# LED_Monitor.net
KiCad netlist of a schematic drawn in Altium Designer
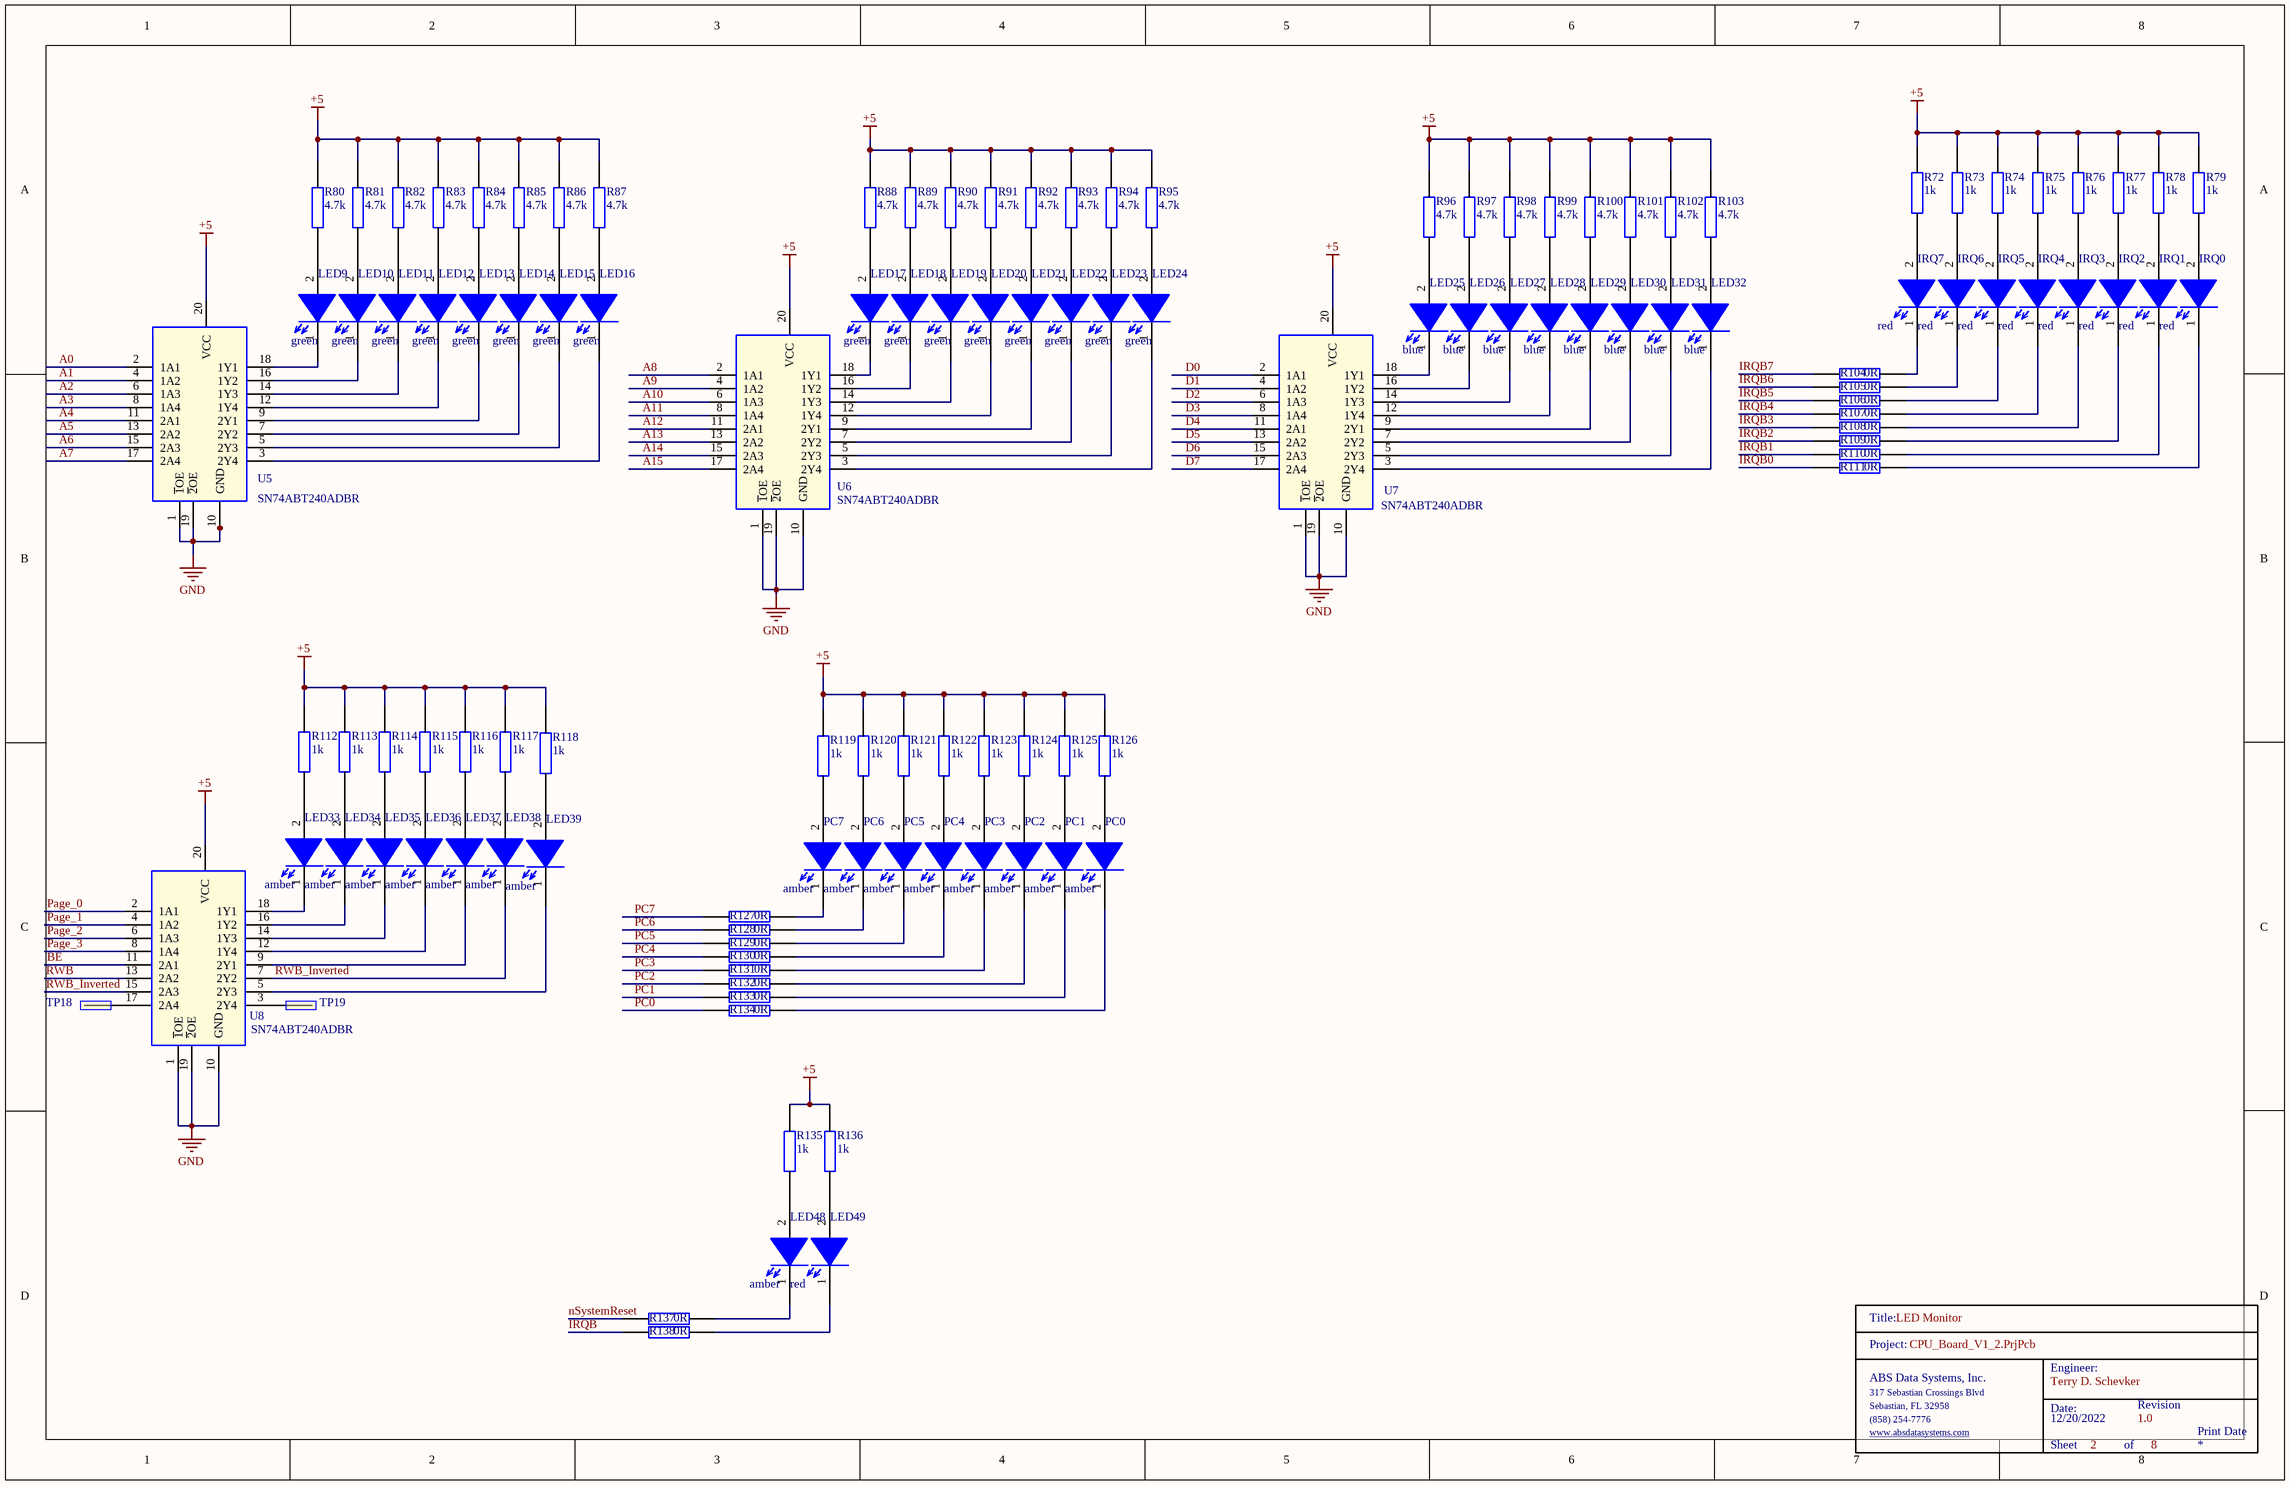
[diagram p0: LED_Monitor.SchDoc]

(export (version "E")
  (design (tool "Eeschema 10.0.6"))
  (components
    (comp (ref "IRQ0")
      (value "red")
      (footprint "0603_Diode")
      (description "Wurth Elektronik 0603 red")
      (fields
        (field (name "MANUFACTURER") "Wurth Electronics")
        (field (name "MANUFACTURER PART NUMBER") "150060GS75000")
      )
      (libsource (lib "Misc") (part "150060RS75000"))
    )
    (comp (ref "IRQ1")
      (value "red")
      (footprint "0603_Diode")
      (description "Wurth Elektronik 0603 red")
      (fields
        (field (name "MANUFACTURER") "Wurth Electronics")
        (field (name "MANUFACTURER PART NUMBER") "150060GS75000")
      )
      (libsource (lib "Misc") (part "150060RS75000"))
    )
    (comp (ref "IRQ2")
      (value "red")
      (footprint "0603_Diode")
      (description "Wurth Elektronik 0603 red")
      (fields
        (field (name "MANUFACTURER") "Wurth Electronics")
        (field (name "MANUFACTURER PART NUMBER") "150060GS75000")
      )
      (libsource (lib "Misc") (part "150060RS75000"))
    )
    (comp (ref "IRQ3")
      (value "red")
      (footprint "0603_Diode")
      (description "Wurth Elektronik 0603 red")
      (fields
        (field (name "MANUFACTURER") "Wurth Electronics")
        (field (name "MANUFACTURER PART NUMBER") "150060GS75000")
      )
      (libsource (lib "Misc") (part "150060RS75000"))
    )
    (comp (ref "IRQ4")
      (value "red")
      (footprint "0603_Diode")
      (description "Wurth Elektronik 0603 red")
      (fields
        (field (name "MANUFACTURER") "Wurth Electronics")
        (field (name "MANUFACTURER PART NUMBER") "150060GS75000")
      )
      (libsource (lib "Misc") (part "150060RS75000"))
    )
    (comp (ref "IRQ5")
      (value "red")
      (footprint "0603_Diode")
      (description "Wurth Elektronik 0603 red")
      (fields
        (field (name "MANUFACTURER") "Wurth Electronics")
        (field (name "MANUFACTURER PART NUMBER") "150060GS75000")
      )
      (libsource (lib "Misc") (part "150060RS75000"))
    )
    (comp (ref "IRQ6")
      (value "red")
      (footprint "0603_Diode")
      (description "Wurth Elektronik 0603 red")
      (fields
        (field (name "MANUFACTURER") "Wurth Electronics")
        (field (name "MANUFACTURER PART NUMBER") "150060GS75000")
      )
      (libsource (lib "Misc") (part "150060RS75000"))
    )
    (comp (ref "IRQ7")
      (value "red")
      (footprint "0603_Diode")
      (description "Wurth Elektronik 0603 red")
      (fields
        (field (name "MANUFACTURER") "Wurth Electronics")
        (field (name "MANUFACTURER PART NUMBER") "150060GS75000")
      )
      (libsource (lib "Misc") (part "150060RS75000"))
    )
    (comp (ref "LED9")
      (value "green")
      (footprint "0603_Diode")
      (description "Wurth Elektronik 0603 green")
      (fields
        (field (name "MANUFACTURER") "Wurth Electronics")
        (field (name "MANUFACTURER PART NUMBER") "150060GS75000")
      )
      (libsource (lib "Misc") (part "150060GS75000"))
    )
    (comp (ref "LED10")
      (value "green")
      (footprint "0603_Diode")
      (description "Wurth Elektronik 0603 green")
      (fields
        (field (name "MANUFACTURER") "Wurth Electronics")
        (field (name "MANUFACTURER PART NUMBER") "150060GS75000")
      )
      (libsource (lib "Misc") (part "150060GS75000"))
    )
    (comp (ref "LED11")
      (value "green")
      (footprint "0603_Diode")
      (description "Wurth Elektronik 0603 green")
      (fields
        (field (name "MANUFACTURER") "Wurth Electronics")
        (field (name "MANUFACTURER PART NUMBER") "150060GS75000")
      )
      (libsource (lib "Misc") (part "150060GS75000"))
    )
    (comp (ref "LED12")
      (value "green")
      (footprint "0603_Diode")
      (description "Wurth Elektronik 0603 green")
      (fields
        (field (name "MANUFACTURER") "Wurth Electronics")
        (field (name "MANUFACTURER PART NUMBER") "150060GS75000")
      )
      (libsource (lib "Misc") (part "150060GS75000"))
    )
    (comp (ref "LED13")
      (value "green")
      (footprint "0603_Diode")
      (description "Wurth Elektronik 0603 green")
      (fields
        (field (name "MANUFACTURER") "Wurth Electronics")
        (field (name "MANUFACTURER PART NUMBER") "150060GS75000")
      )
      (libsource (lib "Misc") (part "150060GS75000"))
    )
    (comp (ref "LED14")
      (value "green")
      (footprint "0603_Diode")
      (description "Wurth Elektronik 0603 green")
      (fields
        (field (name "MANUFACTURER") "Wurth Electronics")
        (field (name "MANUFACTURER PART NUMBER") "150060GS75000")
      )
      (libsource (lib "Misc") (part "150060GS75000"))
    )
    (comp (ref "LED15")
      (value "green")
      (footprint "0603_Diode")
      (description "Wurth Elektronik 0603 green")
      (fields
        (field (name "MANUFACTURER") "Wurth Electronics")
        (field (name "MANUFACTURER PART NUMBER") "150060GS75000")
      )
      (libsource (lib "Misc") (part "150060GS75000"))
    )
    (comp (ref "LED16")
      (value "green")
      (footprint "0603_Diode")
      (description "Wurth Elektronik 0603 green")
      (fields
        (field (name "MANUFACTURER") "Wurth Electronics")
        (field (name "MANUFACTURER PART NUMBER") "150060GS75000")
      )
      (libsource (lib "Misc") (part "150060GS75000"))
    )
    (comp (ref "LED17")
      (value "green")
      (footprint "0603_Diode")
      (description "Wurth Elektronik 0603 green")
      (fields
        (field (name "MANUFACTURER") "Wurth Electronics")
        (field (name "MANUFACTURER PART NUMBER") "150060GS75000")
      )
      (libsource (lib "Misc") (part "150060GS75000"))
    )
    (comp (ref "LED18")
      (value "green")
      (footprint "0603_Diode")
      (description "Wurth Elektronik 0603 green")
      (fields
        (field (name "MANUFACTURER") "Wurth Electronics")
        (field (name "MANUFACTURER PART NUMBER") "150060GS75000")
      )
      (libsource (lib "Misc") (part "150060GS75000"))
    )
    (comp (ref "LED19")
      (value "green")
      (footprint "0603_Diode")
      (description "Wurth Elektronik 0603 green")
      (fields
        (field (name "MANUFACTURER") "Wurth Electronics")
        (field (name "MANUFACTURER PART NUMBER") "150060GS75000")
      )
      (libsource (lib "Misc") (part "150060GS75000"))
    )
    (comp (ref "LED20")
      (value "green")
      (footprint "0603_Diode")
      (description "Wurth Elektronik 0603 green")
      (fields
        (field (name "MANUFACTURER") "Wurth Electronics")
        (field (name "MANUFACTURER PART NUMBER") "150060GS75000")
      )
      (libsource (lib "Misc") (part "150060GS75000"))
    )
    (comp (ref "LED21")
      (value "green")
      (footprint "0603_Diode")
      (description "Wurth Elektronik 0603 green")
      (fields
        (field (name "MANUFACTURER") "Wurth Electronics")
        (field (name "MANUFACTURER PART NUMBER") "150060GS75000")
      )
      (libsource (lib "Misc") (part "150060GS75000"))
    )
    (comp (ref "LED22")
      (value "green")
      (footprint "0603_Diode")
      (description "Wurth Elektronik 0603 green")
      (fields
        (field (name "MANUFACTURER") "Wurth Electronics")
        (field (name "MANUFACTURER PART NUMBER") "150060GS75000")
      )
      (libsource (lib "Misc") (part "150060GS75000"))
    )
    (comp (ref "LED23")
      (value "green")
      (footprint "0603_Diode")
      (description "Wurth Elektronik 0603 green")
      (fields
        (field (name "MANUFACTURER") "Wurth Electronics")
        (field (name "MANUFACTURER PART NUMBER") "150060GS75000")
      )
      (libsource (lib "Misc") (part "150060GS75000"))
    )
    (comp (ref "LED24")
      (value "green")
      (footprint "0603_Diode")
      (description "Wurth Elektronik 0603 green")
      (fields
        (field (name "MANUFACTURER") "Wurth Electronics")
        (field (name "MANUFACTURER PART NUMBER") "150060GS75000")
      )
      (libsource (lib "Misc") (part "150060GS75000"))
    )
    (comp (ref "LED25")
      (value "blue")
      (footprint "0603_Diode")
      (description "Wurth Elektronik 0603 blue")
      (fields
        (field (name "MANUFACTURER") "Wurth Electronics")
        (field (name "MANUFACTURER PART NUMBER") "150060GS75000")
      )
      (libsource (lib "Misc") (part "150060BS75000"))
    )
    (comp (ref "LED26")
      (value "blue")
      (footprint "0603_Diode")
      (description "Wurth Elektronik 0603 blue")
      (fields
        (field (name "MANUFACTURER") "Wurth Electronics")
        (field (name "MANUFACTURER PART NUMBER") "150060GS75000")
      )
      (libsource (lib "Misc") (part "150060BS75000"))
    )
    (comp (ref "LED27")
      (value "blue")
      (footprint "0603_Diode")
      (description "Wurth Elektronik 0603 blue")
      (fields
        (field (name "MANUFACTURER") "Wurth Electronics")
        (field (name "MANUFACTURER PART NUMBER") "150060GS75000")
      )
      (libsource (lib "Misc") (part "150060BS75000"))
    )
    (comp (ref "LED28")
      (value "blue")
      (footprint "0603_Diode")
      (description "Wurth Elektronik 0603 blue")
      (fields
        (field (name "MANUFACTURER") "Wurth Electronics")
        (field (name "MANUFACTURER PART NUMBER") "150060GS75000")
      )
      (libsource (lib "Misc") (part "150060BS75000"))
    )
    (comp (ref "LED29")
      (value "blue")
      (footprint "0603_Diode")
      (description "Wurth Elektronik 0603 blue")
      (fields
        (field (name "MANUFACTURER") "Wurth Electronics")
        (field (name "MANUFACTURER PART NUMBER") "150060GS75000")
      )
      (libsource (lib "Misc") (part "150060BS75000"))
    )
    (comp (ref "LED30")
      (value "blue")
      (footprint "0603_Diode")
      (description "Wurth Elektronik 0603 blue")
      (fields
        (field (name "MANUFACTURER") "Wurth Electronics")
        (field (name "MANUFACTURER PART NUMBER") "150060GS75000")
      )
      (libsource (lib "Misc") (part "150060BS75000"))
    )
    (comp (ref "LED31")
      (value "blue")
      (footprint "0603_Diode")
      (description "Wurth Elektronik 0603 blue")
      (fields
        (field (name "MANUFACTURER") "Wurth Electronics")
        (field (name "MANUFACTURER PART NUMBER") "150060GS75000")
      )
      (libsource (lib "Misc") (part "150060BS75000"))
    )
    (comp (ref "LED32")
      (value "blue")
      (footprint "0603_Diode")
      (description "Wurth Elektronik 0603 blue")
      (fields
        (field (name "MANUFACTURER") "Wurth Electronics")
        (field (name "MANUFACTURER PART NUMBER") "150060GS75000")
      )
      (libsource (lib "Misc") (part "150060BS75000"))
    )
    (comp (ref "LED33")
      (value "amber")
      (footprint "0603_Diode")
      (description "Wurth Elektronik 0603 amber")
      (fields
        (field (name "MANUFACTURER") "Wurth Electronics")
        (field (name "MANUFACTURER PART NUMBER") "150060GS75000")
      )
      (libsource (lib "Misc") (part "150060AS75000"))
    )
    (comp (ref "LED34")
      (value "amber")
      (footprint "0603_Diode")
      (description "Wurth Elektronik 0603 amber")
      (fields
        (field (name "MANUFACTURER") "Wurth Electronics")
        (field (name "MANUFACTURER PART NUMBER") "150060GS75000")
      )
      (libsource (lib "Misc") (part "150060AS75000"))
    )
    (comp (ref "LED35")
      (value "amber")
      (footprint "0603_Diode")
      (description "Wurth Elektronik 0603 amber")
      (fields
        (field (name "MANUFACTURER") "Wurth Electronics")
        (field (name "MANUFACTURER PART NUMBER") "150060GS75000")
      )
      (libsource (lib "Misc") (part "150060AS75000"))
    )
    (comp (ref "LED36")
      (value "amber")
      (footprint "0603_Diode")
      (description "Wurth Elektronik 0603 amber")
      (fields
        (field (name "MANUFACTURER") "Wurth Electronics")
        (field (name "MANUFACTURER PART NUMBER") "150060GS75000")
      )
      (libsource (lib "Misc") (part "150060AS75000"))
    )
    (comp (ref "LED37")
      (value "amber")
      (footprint "0603_Diode")
      (description "Wurth Elektronik 0603 amber")
      (fields
        (field (name "MANUFACTURER") "Wurth Electronics")
        (field (name "MANUFACTURER PART NUMBER") "150060GS75000")
      )
      (libsource (lib "Misc") (part "150060AS75000"))
    )
    (comp (ref "LED38")
      (value "amber")
      (footprint "0603_Diode")
      (description "Wurth Elektronik 0603 amber")
      (fields
        (field (name "MANUFACTURER") "Wurth Electronics")
        (field (name "MANUFACTURER PART NUMBER") "150060GS75000")
      )
      (libsource (lib "Misc") (part "150060AS75000"))
    )
    (comp (ref "LED39")
      (value "amber")
      (footprint "0603_Diode")
      (description "Wurth Elektronik 0603 amber")
      (fields
        (field (name "MANUFACTURER") "Wurth Electronics")
        (field (name "MANUFACTURER PART NUMBER") "150060GS75000")
      )
      (libsource (lib "Misc") (part "150060AS75000"))
    )
    (comp (ref "LED48")
      (value "amber")
      (footprint "0603_Diode")
      (description "Wurth Elektronik 0603 amber")
      (fields
        (field (name "MANUFACTURER") "Wurth Electronics")
        (field (name "MANUFACTURER PART NUMBER") "150060GS75000")
      )
      (libsource (lib "Misc") (part "150060AS75000"))
    )
    (comp (ref "LED49")
      (value "red")
      (footprint "0603_Diode")
      (description "Wurth Elektronik 0603 red")
      (fields
        (field (name "MANUFACTURER") "Wurth Electronics")
        (field (name "MANUFACTURER PART NUMBER") "150060GS75000")
      )
      (libsource (lib "Misc") (part "150060RS75000"))
    )
    (comp (ref "PC0")
      (value "amber")
      (footprint "0603_Diode")
      (description "Wurth Elektronik 0603 amber")
      (fields
        (field (name "MANUFACTURER") "Wurth Electronics")
        (field (name "MANUFACTURER PART NUMBER") "150060GS75000")
      )
      (libsource (lib "Misc") (part "150060AS75000"))
    )
    (comp (ref "PC1")
      (value "amber")
      (footprint "0603_Diode")
      (description "Wurth Elektronik 0603 amber")
      (fields
        (field (name "MANUFACTURER") "Wurth Electronics")
        (field (name "MANUFACTURER PART NUMBER") "150060GS75000")
      )
      (libsource (lib "Misc") (part "150060AS75000"))
    )
    (comp (ref "PC2")
      (value "amber")
      (footprint "0603_Diode")
      (description "Wurth Elektronik 0603 amber")
      (fields
        (field (name "MANUFACTURER") "Wurth Electronics")
        (field (name "MANUFACTURER PART NUMBER") "150060GS75000")
      )
      (libsource (lib "Misc") (part "150060AS75000"))
    )
    (comp (ref "PC3")
      (value "amber")
      (footprint "0603_Diode")
      (description "Wurth Elektronik 0603 amber")
      (fields
        (field (name "MANUFACTURER") "Wurth Electronics")
        (field (name "MANUFACTURER PART NUMBER") "150060GS75000")
      )
      (libsource (lib "Misc") (part "150060AS75000"))
    )
    (comp (ref "PC4")
      (value "amber")
      (footprint "0603_Diode")
      (description "Wurth Elektronik 0603 amber")
      (fields
        (field (name "MANUFACTURER") "Wurth Electronics")
        (field (name "MANUFACTURER PART NUMBER") "150060GS75000")
      )
      (libsource (lib "Misc") (part "150060AS75000"))
    )
    (comp (ref "PC5")
      (value "amber")
      (footprint "0603_Diode")
      (description "Wurth Elektronik 0603 amber")
      (fields
        (field (name "MANUFACTURER") "Wurth Electronics")
        (field (name "MANUFACTURER PART NUMBER") "150060GS75000")
      )
      (libsource (lib "Misc") (part "150060AS75000"))
    )
    (comp (ref "PC6")
      (value "amber")
      (footprint "0603_Diode")
      (description "Wurth Elektronik 0603 amber")
      (fields
        (field (name "MANUFACTURER") "Wurth Electronics")
        (field (name "MANUFACTURER PART NUMBER") "150060GS75000")
      )
      (libsource (lib "Misc") (part "150060AS75000"))
    )
    (comp (ref "PC7")
      (value "amber")
      (footprint "0603_Diode")
      (description "Wurth Elektronik 0603 amber")
      (fields
        (field (name "MANUFACTURER") "Wurth Electronics")
        (field (name "MANUFACTURER PART NUMBER") "150060GS75000")
      )
      (libsource (lib "Misc") (part "150060AS75000"))
    )
    (comp (ref "R72")
      (value "1k")
      (footprint "0603")
      (description "YAGEO 0603 1k ohm")
      (fields
        (field (name "MOUSER PART NUMBER") "603-RC0603JR-070RL")
        (field (name "MANUFACTURER_PART_NUMBER") "RC0603JR-070RL")
      )
      (libsource (lib "Resistors") (part "AC0603FR-7W1KL_1"))
    )
    (comp (ref "R73")
      (value "1k")
      (footprint "0603")
      (description "YAGEO 0603 1k ohm")
      (fields
        (field (name "MOUSER PART NUMBER") "603-RC0603JR-070RL")
        (field (name "MANUFACTURER_PART_NUMBER") "RC0603JR-070RL")
      )
      (libsource (lib "Resistors") (part "AC0603FR-7W1KL_1"))
    )
    (comp (ref "R74")
      (value "1k")
      (footprint "0603")
      (description "YAGEO 0603 1k ohm")
      (fields
        (field (name "MOUSER PART NUMBER") "603-RC0603JR-070RL")
        (field (name "MANUFACTURER_PART_NUMBER") "RC0603JR-070RL")
      )
      (libsource (lib "Resistors") (part "AC0603FR-7W1KL_1"))
    )
    (comp (ref "R75")
      (value "1k")
      (footprint "0603")
      (description "YAGEO 0603 1k ohm")
      (fields
        (field (name "MOUSER PART NUMBER") "603-RC0603JR-070RL")
        (field (name "MANUFACTURER_PART_NUMBER") "RC0603JR-070RL")
      )
      (libsource (lib "Resistors") (part "AC0603FR-7W1KL_1"))
    )
    (comp (ref "R76")
      (value "1k")
      (footprint "0603")
      (description "YAGEO 0603 1k ohm")
      (fields
        (field (name "MOUSER PART NUMBER") "603-RC0603JR-070RL")
        (field (name "MANUFACTURER_PART_NUMBER") "RC0603JR-070RL")
      )
      (libsource (lib "Resistors") (part "AC0603FR-7W1KL_1"))
    )
    (comp (ref "R77")
      (value "1k")
      (footprint "0603")
      (description "YAGEO 0603 1k ohm")
      (fields
        (field (name "MOUSER PART NUMBER") "603-RC0603JR-070RL")
        (field (name "MANUFACTURER_PART_NUMBER") "RC0603JR-070RL")
      )
      (libsource (lib "Resistors") (part "AC0603FR-7W1KL_1"))
    )
    (comp (ref "R78")
      (value "1k")
      (footprint "0603")
      (description "YAGEO 0603 1k ohm")
      (fields
        (field (name "MOUSER PART NUMBER") "603-RC0603JR-070RL")
        (field (name "MANUFACTURER_PART_NUMBER") "RC0603JR-070RL")
      )
      (libsource (lib "Resistors") (part "AC0603FR-7W1KL_1"))
    )
    (comp (ref "R79")
      (value "1k")
      (footprint "0603")
      (description "YAGEO 0603 1k ohm")
      (fields
        (field (name "MOUSER PART NUMBER") "603-RC0603JR-070RL")
        (field (name "MANUFACTURER_PART_NUMBER") "RC0603JR-070RL")
      )
      (libsource (lib "Resistors") (part "AC0603FR-7W1KL_1"))
    )
    (comp (ref "R80")
      (value "4.7k")
      (footprint "0603")
      (description "YAGEO 0603 4.7k")
      (fields
        (field (name "MOUSER PART NUMBER") "603-RC0603JR-070RL")
        (field (name "MANUFACTURER_PART_NUMBER") "RC0603JR-070RL")
      )
      (libsource (lib "Resistors") (part "RC0603FR-104K7L"))
    )
    (comp (ref "R81")
      (value "4.7k")
      (footprint "0603")
      (description "YAGEO 0603 4.7k")
      (fields
        (field (name "MOUSER PART NUMBER") "603-RC0603JR-070RL")
        (field (name "MANUFACTURER_PART_NUMBER") "RC0603JR-070RL")
      )
      (libsource (lib "Resistors") (part "RC0603FR-104K7L"))
    )
    (comp (ref "R82")
      (value "4.7k")
      (footprint "0603")
      (description "YAGEO 0603 4.7k")
      (fields
        (field (name "MOUSER PART NUMBER") "603-RC0603JR-070RL")
        (field (name "MANUFACTURER_PART_NUMBER") "RC0603JR-070RL")
      )
      (libsource (lib "Resistors") (part "RC0603FR-104K7L"))
    )
    (comp (ref "R83")
      (value "4.7k")
      (footprint "0603")
      (description "YAGEO 0603 4.7k")
      (fields
        (field (name "MOUSER PART NUMBER") "603-RC0603JR-070RL")
        (field (name "MANUFACTURER_PART_NUMBER") "RC0603JR-070RL")
      )
      (libsource (lib "Resistors") (part "RC0603FR-104K7L"))
    )
    (comp (ref "R84")
      (value "4.7k")
      (footprint "0603")
      (description "YAGEO 0603 4.7k")
      (fields
        (field (name "MOUSER PART NUMBER") "603-RC0603JR-070RL")
        (field (name "MANUFACTURER_PART_NUMBER") "RC0603JR-070RL")
      )
      (libsource (lib "Resistors") (part "RC0603FR-104K7L"))
    )
    (comp (ref "R85")
      (value "4.7k")
      (footprint "0603")
      (description "YAGEO 0603 4.7k")
      (fields
        (field (name "MOUSER PART NUMBER") "603-RC0603JR-070RL")
        (field (name "MANUFACTURER_PART_NUMBER") "RC0603JR-070RL")
      )
      (libsource (lib "Resistors") (part "RC0603FR-104K7L"))
    )
    (comp (ref "R86")
      (value "4.7k")
      (footprint "0603")
      (description "YAGEO 0603 4.7k")
      (fields
        (field (name "MOUSER PART NUMBER") "603-RC0603JR-070RL")
        (field (name "MANUFACTURER_PART_NUMBER") "RC0603JR-070RL")
      )
      (libsource (lib "Resistors") (part "RC0603FR-104K7L"))
    )
    (comp (ref "R87")
      (value "4.7k")
      (footprint "0603")
      (description "YAGEO 0603 4.7k")
      (fields
        (field (name "MOUSER PART NUMBER") "603-RC0603JR-070RL")
        (field (name "MANUFACTURER_PART_NUMBER") "RC0603JR-070RL")
      )
      (libsource (lib "Resistors") (part "RC0603FR-104K7L"))
    )
    (comp (ref "R88")
      (value "4.7k")
      (footprint "0603")
      (description "YAGEO 0603 4.7k")
      (fields
        (field (name "MOUSER PART NUMBER") "603-RC0603JR-070RL")
        (field (name "MANUFACTURER_PART_NUMBER") "RC0603JR-070RL")
      )
      (libsource (lib "Resistors") (part "RC0603FR-104K7L"))
    )
    (comp (ref "R89")
      (value "4.7k")
      (footprint "0603")
      (description "YAGEO 0603 4.7k")
      (fields
        (field (name "MOUSER PART NUMBER") "603-RC0603JR-070RL")
        (field (name "MANUFACTURER_PART_NUMBER") "RC0603JR-070RL")
      )
      (libsource (lib "Resistors") (part "RC0603FR-104K7L"))
    )
    (comp (ref "R90")
      (value "4.7k")
      (footprint "0603")
      (description "YAGEO 0603 4.7k")
      (fields
        (field (name "MOUSER PART NUMBER") "603-RC0603JR-070RL")
        (field (name "MANUFACTURER_PART_NUMBER") "RC0603JR-070RL")
      )
      (libsource (lib "Resistors") (part "RC0603FR-104K7L"))
    )
    (comp (ref "R91")
      (value "4.7k")
      (footprint "0603")
      (description "YAGEO 0603 4.7k")
      (fields
        (field (name "MOUSER PART NUMBER") "603-RC0603JR-070RL")
        (field (name "MANUFACTURER_PART_NUMBER") "RC0603JR-070RL")
      )
      (libsource (lib "Resistors") (part "RC0603FR-104K7L"))
    )
    (comp (ref "R92")
      (value "4.7k")
      (footprint "0603")
      (description "YAGEO 0603 4.7k")
      (fields
        (field (name "MOUSER PART NUMBER") "603-RC0603JR-070RL")
        (field (name "MANUFACTURER_PART_NUMBER") "RC0603JR-070RL")
      )
      (libsource (lib "Resistors") (part "RC0603FR-104K7L"))
    )
    (comp (ref "R93")
      (value "4.7k")
      (footprint "0603")
      (description "YAGEO 0603 4.7k")
      (fields
        (field (name "MOUSER PART NUMBER") "603-RC0603JR-070RL")
        (field (name "MANUFACTURER_PART_NUMBER") "RC0603JR-070RL")
      )
      (libsource (lib "Resistors") (part "RC0603FR-104K7L"))
    )
    (comp (ref "R94")
      (value "4.7k")
      (footprint "0603")
      (description "YAGEO 0603 4.7k")
      (fields
        (field (name "MOUSER PART NUMBER") "603-RC0603JR-070RL")
        (field (name "MANUFACTURER_PART_NUMBER") "RC0603JR-070RL")
      )
      (libsource (lib "Resistors") (part "RC0603FR-104K7L"))
    )
    (comp (ref "R95")
      (value "4.7k")
      (footprint "0603")
      (description "YAGEO 0603 4.7k")
      (fields
        (field (name "MOUSER PART NUMBER") "603-RC0603JR-070RL")
        (field (name "MANUFACTURER_PART_NUMBER") "RC0603JR-070RL")
      )
      (libsource (lib "Resistors") (part "RC0603FR-104K7L"))
    )
    (comp (ref "R96")
      (value "4.7k")
      (footprint "0603")
      (description "YAGEO 0603 4.7k")
      (fields
        (field (name "MOUSER PART NUMBER") "603-RC0603JR-070RL")
        (field (name "MANUFACTURER_PART_NUMBER") "RC0603JR-070RL")
      )
      (libsource (lib "Resistors") (part "RC0603FR-104K7L"))
    )
    (comp (ref "R97")
      (value "4.7k")
      (footprint "0603")
      (description "YAGEO 0603 4.7k")
      (fields
        (field (name "MOUSER PART NUMBER") "603-RC0603JR-070RL")
        (field (name "MANUFACTURER_PART_NUMBER") "RC0603JR-070RL")
      )
      (libsource (lib "Resistors") (part "RC0603FR-104K7L"))
    )
    (comp (ref "R98")
      (value "4.7k")
      (footprint "0603")
      (description "YAGEO 0603 4.7k")
      (fields
        (field (name "MOUSER PART NUMBER") "603-RC0603JR-070RL")
        (field (name "MANUFACTURER_PART_NUMBER") "RC0603JR-070RL")
      )
      (libsource (lib "Resistors") (part "RC0603FR-104K7L"))
    )
    (comp (ref "R99")
      (value "4.7k")
      (footprint "0603")
      (description "YAGEO 0603 4.7k")
      (fields
        (field (name "MOUSER PART NUMBER") "603-RC0603JR-070RL")
        (field (name "MANUFACTURER_PART_NUMBER") "RC0603JR-070RL")
      )
      (libsource (lib "Resistors") (part "RC0603FR-104K7L"))
    )
    (comp (ref "R100")
      (value "4.7k")
      (footprint "0603")
      (description "YAGEO 0603 4.7k")
      (fields
        (field (name "MOUSER PART NUMBER") "603-RC0603JR-070RL")
        (field (name "MANUFACTURER_PART_NUMBER") "RC0603JR-070RL")
      )
      (libsource (lib "Resistors") (part "RC0603FR-104K7L"))
    )
    (comp (ref "R101")
      (value "4.7k")
      (footprint "0603")
      (description "YAGEO 0603 4.7k")
      (fields
        (field (name "MOUSER PART NUMBER") "603-RC0603JR-070RL")
        (field (name "MANUFACTURER_PART_NUMBER") "RC0603JR-070RL")
      )
      (libsource (lib "Resistors") (part "RC0603FR-104K7L"))
    )
    (comp (ref "R102")
      (value "4.7k")
      (footprint "0603")
      (description "YAGEO 0603 4.7k")
      (fields
        (field (name "MOUSER PART NUMBER") "603-RC0603JR-070RL")
        (field (name "MANUFACTURER_PART_NUMBER") "RC0603JR-070RL")
      )
      (libsource (lib "Resistors") (part "RC0603FR-104K7L"))
    )
    (comp (ref "R103")
      (value "4.7k")
      (footprint "0603")
      (description "YAGEO 0603 4.7k")
      (fields
        (field (name "MOUSER PART NUMBER") "603-RC0603JR-070RL")
        (field (name "MANUFACTURER_PART_NUMBER") "RC0603JR-070RL")
      )
      (libsource (lib "Resistors") (part "RC0603FR-104K7L"))
    )
    (comp (ref "R104")
      (value "0R")
      (footprint "0603")
      (description "YAGEO 0603 0 ohm")
      (fields
        (field (name "MOUSER PART NUMBER") "603-RC0603JR-070RL")
        (field (name "MANUFACTURER_PART_NUMBER") "RC0603JR-070RL")
      )
      (libsource (lib "Resistors") (part "RC0603JR-070RL"))
    )
    (comp (ref "R105")
      (value "0R")
      (footprint "0603")
      (description "YAGEO 0603 0 ohm")
      (fields
        (field (name "MOUSER PART NUMBER") "603-RC0603JR-070RL")
        (field (name "MANUFACTURER_PART_NUMBER") "RC0603JR-070RL")
      )
      (libsource (lib "Resistors") (part "RC0603JR-070RL"))
    )
    (comp (ref "R106")
      (value "0R")
      (footprint "0603")
      (description "YAGEO 0603 0 ohm")
      (fields
        (field (name "MOUSER PART NUMBER") "603-RC0603JR-070RL")
        (field (name "MANUFACTURER_PART_NUMBER") "RC0603JR-070RL")
      )
      (libsource (lib "Resistors") (part "RC0603JR-070RL"))
    )
    (comp (ref "R107")
      (value "0R")
      (footprint "0603")
      (description "YAGEO 0603 0 ohm")
      (fields
        (field (name "MOUSER PART NUMBER") "603-RC0603JR-070RL")
        (field (name "MANUFACTURER_PART_NUMBER") "RC0603JR-070RL")
      )
      (libsource (lib "Resistors") (part "RC0603JR-070RL"))
    )
    (comp (ref "R108")
      (value "0R")
      (footprint "0603")
      (description "YAGEO 0603 0 ohm")
      (fields
        (field (name "MOUSER PART NUMBER") "603-RC0603JR-070RL")
        (field (name "MANUFACTURER_PART_NUMBER") "RC0603JR-070RL")
      )
      (libsource (lib "Resistors") (part "RC0603JR-070RL"))
    )
    (comp (ref "R109")
      (value "0R")
      (footprint "0603")
      (description "YAGEO 0603 0 ohm")
      (fields
        (field (name "MOUSER PART NUMBER") "603-RC0603JR-070RL")
        (field (name "MANUFACTURER_PART_NUMBER") "RC0603JR-070RL")
      )
      (libsource (lib "Resistors") (part "RC0603JR-070RL"))
    )
    (comp (ref "R110")
      (value "0R")
      (footprint "0603")
      (description "YAGEO 0603 0 ohm")
      (fields
        (field (name "MOUSER PART NUMBER") "603-RC0603JR-070RL")
        (field (name "MANUFACTURER_PART_NUMBER") "RC0603JR-070RL")
      )
      (libsource (lib "Resistors") (part "RC0603JR-070RL"))
    )
    (comp (ref "R111")
      (value "0R")
      (footprint "0603")
      (description "YAGEO 0603 0 ohm")
      (fields
        (field (name "MOUSER PART NUMBER") "603-RC0603JR-070RL")
        (field (name "MANUFACTURER_PART_NUMBER") "RC0603JR-070RL")
      )
      (libsource (lib "Resistors") (part "RC0603JR-070RL"))
    )
    (comp (ref "R112")
      (value "1k")
      (footprint "0603")
      (description "YAGEO 0603 1k ohm")
      (fields
        (field (name "MOUSER PART NUMBER") "603-RC0603JR-070RL")
        (field (name "MANUFACTURER_PART_NUMBER") "RC0603JR-070RL")
      )
      (libsource (lib "Resistors") (part "AC0603FR-7W1KL_1"))
    )
    (comp (ref "R113")
      (value "1k")
      (footprint "0603")
      (description "YAGEO 0603 1k ohm")
      (fields
        (field (name "MOUSER PART NUMBER") "603-RC0603JR-070RL")
        (field (name "MANUFACTURER_PART_NUMBER") "RC0603JR-070RL")
      )
      (libsource (lib "Resistors") (part "AC0603FR-7W1KL_1"))
    )
    (comp (ref "R114")
      (value "1k")
      (footprint "0603")
      (description "YAGEO 0603 1k ohm")
      (fields
        (field (name "MOUSER PART NUMBER") "603-RC0603JR-070RL")
        (field (name "MANUFACTURER_PART_NUMBER") "RC0603JR-070RL")
      )
      (libsource (lib "Resistors") (part "AC0603FR-7W1KL_1"))
    )
    (comp (ref "R115")
      (value "1k")
      (footprint "0603")
      (description "YAGEO 0603 1k ohm")
      (fields
        (field (name "MOUSER PART NUMBER") "603-RC0603JR-070RL")
        (field (name "MANUFACTURER_PART_NUMBER") "RC0603JR-070RL")
      )
      (libsource (lib "Resistors") (part "AC0603FR-7W1KL_1"))
    )
    (comp (ref "R116")
      (value "1k")
      (footprint "0603")
      (description "YAGEO 0603 1k ohm")
      (fields
        (field (name "MOUSER PART NUMBER") "603-RC0603JR-070RL")
        (field (name "MANUFACTURER_PART_NUMBER") "RC0603JR-070RL")
      )
      (libsource (lib "Resistors") (part "AC0603FR-7W1KL_1"))
    )
    (comp (ref "R117")
      (value "1k")
      (footprint "0603")
      (description "YAGEO 0603 1k ohm")
      (fields
        (field (name "MOUSER PART NUMBER") "603-RC0603JR-070RL")
        (field (name "MANUFACTURER_PART_NUMBER") "RC0603JR-070RL")
      )
      (libsource (lib "Resistors") (part "AC0603FR-7W1KL_1"))
    )
    (comp (ref "R118")
      (value "1k")
      (footprint "0603")
      (description "YAGEO 0603 1k ohm")
      (fields
        (field (name "MOUSER PART NUMBER") "603-RC0603JR-070RL")
        (field (name "MANUFACTURER_PART_NUMBER") "RC0603JR-070RL")
      )
      (libsource (lib "Resistors") (part "AC0603FR-7W1KL_1"))
    )
    (comp (ref "R119")
      (value "1k")
      (footprint "0603")
      (description "YAGEO 0603 1k ohm")
      (fields
        (field (name "MOUSER PART NUMBER") "603-RC0603JR-070RL")
        (field (name "MANUFACTURER_PART_NUMBER") "RC0603JR-070RL")
      )
      (libsource (lib "Resistors") (part "AC0603FR-7W1KL_1"))
    )
    (comp (ref "R120")
      (value "1k")
      (footprint "0603")
      (description "YAGEO 0603 1k ohm")
      (fields
        (field (name "MOUSER PART NUMBER") "603-RC0603JR-070RL")
        (field (name "MANUFACTURER_PART_NUMBER") "RC0603JR-070RL")
      )
      (libsource (lib "Resistors") (part "AC0603FR-7W1KL_1"))
    )
    (comp (ref "R121")
      (value "1k")
      (footprint "0603")
      (description "YAGEO 0603 1k ohm")
      (fields
        (field (name "MOUSER PART NUMBER") "603-RC0603JR-070RL")
        (field (name "MANUFACTURER_PART_NUMBER") "RC0603JR-070RL")
      )
      (libsource (lib "Resistors") (part "AC0603FR-7W1KL_1"))
    )
    (comp (ref "R122")
      (value "1k")
      (footprint "0603")
      (description "YAGEO 0603 1k ohm")
      (fields
        (field (name "MOUSER PART NUMBER") "603-RC0603JR-070RL")
        (field (name "MANUFACTURER_PART_NUMBER") "RC0603JR-070RL")
      )
      (libsource (lib "Resistors") (part "AC0603FR-7W1KL_1"))
    )
    (comp (ref "R123")
      (value "1k")
      (footprint "0603")
      (description "YAGEO 0603 1k ohm")
      (fields
        (field (name "MOUSER PART NUMBER") "603-RC0603JR-070RL")
        (field (name "MANUFACTURER_PART_NUMBER") "RC0603JR-070RL")
      )
      (libsource (lib "Resistors") (part "AC0603FR-7W1KL_1"))
    )
    (comp (ref "R124")
      (value "1k")
      (footprint "0603")
      (description "YAGEO 0603 1k ohm")
      (fields
        (field (name "MOUSER PART NUMBER") "603-RC0603JR-070RL")
        (field (name "MANUFACTURER_PART_NUMBER") "RC0603JR-070RL")
      )
      (libsource (lib "Resistors") (part "AC0603FR-7W1KL_1"))
    )
    (comp (ref "R125")
      (value "1k")
      (footprint "0603")
      (description "YAGEO 0603 1k ohm")
      (fields
        (field (name "MOUSER PART NUMBER") "603-RC0603JR-070RL")
        (field (name "MANUFACTURER_PART_NUMBER") "RC0603JR-070RL")
      )
      (libsource (lib "Resistors") (part "AC0603FR-7W1KL_1"))
    )
    (comp (ref "R126")
      (value "1k")
      (footprint "0603")
      (description "YAGEO 0603 1k ohm")
      (fields
        (field (name "MOUSER PART NUMBER") "603-RC0603JR-070RL")
        (field (name "MANUFACTURER_PART_NUMBER") "RC0603JR-070RL")
      )
      (libsource (lib "Resistors") (part "AC0603FR-7W1KL_1"))
    )
    (comp (ref "R127")
      (value "0R")
      (footprint "0603")
      (description "YAGEO 0603 0 ohm")
      (fields
        (field (name "MOUSER PART NUMBER") "603-RC0603JR-070RL")
        (field (name "MANUFACTURER_PART_NUMBER") "RC0603JR-070RL")
      )
      (libsource (lib "Resistors") (part "RC0603JR-070RL"))
    )
    (comp (ref "R128")
      (value "0R")
      (footprint "0603")
      (description "YAGEO 0603 0 ohm")
      (fields
        (field (name "MOUSER PART NUMBER") "603-RC0603JR-070RL")
        (field (name "MANUFACTURER_PART_NUMBER") "RC0603JR-070RL")
      )
      (libsource (lib "Resistors") (part "RC0603JR-070RL"))
    )
    (comp (ref "R129")
      (value "0R")
      (footprint "0603")
      (description "YAGEO 0603 0 ohm")
      (fields
        (field (name "MOUSER PART NUMBER") "603-RC0603JR-070RL")
        (field (name "MANUFACTURER_PART_NUMBER") "RC0603JR-070RL")
      )
      (libsource (lib "Resistors") (part "RC0603JR-070RL"))
    )
    (comp (ref "R130")
      (value "0R")
      (footprint "0603")
      (description "YAGEO 0603 0 ohm")
      (fields
        (field (name "MOUSER PART NUMBER") "603-RC0603JR-070RL")
        (field (name "MANUFACTURER_PART_NUMBER") "RC0603JR-070RL")
      )
      (libsource (lib "Resistors") (part "RC0603JR-070RL"))
    )
    (comp (ref "R131")
      (value "0R")
      (footprint "0603")
      (description "YAGEO 0603 0 ohm")
      (fields
        (field (name "MOUSER PART NUMBER") "603-RC0603JR-070RL")
        (field (name "MANUFACTURER_PART_NUMBER") "RC0603JR-070RL")
      )
      (libsource (lib "Resistors") (part "RC0603JR-070RL"))
    )
    (comp (ref "R132")
      (value "0R")
      (footprint "0603")
      (description "YAGEO 0603 0 ohm")
      (fields
        (field (name "MOUSER PART NUMBER") "603-RC0603JR-070RL")
        (field (name "MANUFACTURER_PART_NUMBER") "RC0603JR-070RL")
      )
      (libsource (lib "Resistors") (part "RC0603JR-070RL"))
    )
    (comp (ref "R133")
      (value "0R")
      (footprint "0603")
      (description "YAGEO 0603 0 ohm")
      (fields
        (field (name "MOUSER PART NUMBER") "603-RC0603JR-070RL")
        (field (name "MANUFACTURER_PART_NUMBER") "RC0603JR-070RL")
      )
      (libsource (lib "Resistors") (part "RC0603JR-070RL"))
    )
    (comp (ref "R134")
      (value "0R")
      (footprint "0603")
      (description "YAGEO 0603 0 ohm")
      (fields
        (field (name "MOUSER PART NUMBER") "603-RC0603JR-070RL")
        (field (name "MANUFACTURER_PART_NUMBER") "RC0603JR-070RL")
      )
      (libsource (lib "Resistors") (part "RC0603JR-070RL"))
    )
    (comp (ref "R135")
      (value "1k")
      (footprint "0603")
      (description "YAGEO 0603 1k ohm")
      (fields
        (field (name "MOUSER PART NUMBER") "603-RC0603JR-070RL")
        (field (name "MANUFACTURER_PART_NUMBER") "RC0603JR-070RL")
      )
      (libsource (lib "Resistors") (part "AC0603FR-7W1KL_1"))
    )
    (comp (ref "R136")
      (value "1k")
      (footprint "0603")
      (description "YAGEO 0603 1k ohm")
      (fields
        (field (name "MOUSER PART NUMBER") "603-RC0603JR-070RL")
        (field (name "MANUFACTURER_PART_NUMBER") "RC0603JR-070RL")
      )
      (libsource (lib "Resistors") (part "AC0603FR-7W1KL_1"))
    )
    (comp (ref "R137")
      (value "0R")
      (footprint "0603")
      (description "YAGEO 0603 0 ohm")
      (fields
        (field (name "MOUSER PART NUMBER") "603-RC0603JR-070RL")
        (field (name "MANUFACTURER_PART_NUMBER") "RC0603JR-070RL")
      )
      (libsource (lib "Resistors") (part "RC0603JR-070RL"))
    )
    (comp (ref "R138")
      (value "0R")
      (footprint "0603")
      (description "YAGEO 0603 0 ohm")
      (fields
        (field (name "MOUSER PART NUMBER") "603-RC0603JR-070RL")
        (field (name "MANUFACTURER_PART_NUMBER") "RC0603JR-070RL")
      )
      (libsource (lib "Resistors") (part "RC0603JR-070RL"))
    )
    (comp (ref "TP18")
      (value "TP")
      (footprint "TP")
      (fields
        (field (name "MANUFACTURER") "Samtec")
        (field (name "MANUFACTURER PART NUMBER") "TST-105-01-G-D")
      )
      (libsource (lib "Misc") (part "TP"))
    )
    (comp (ref "TP19")
      (value "TP")
      (footprint "TP")
      (fields
        (field (name "MANUFACTURER") "Samtec")
        (field (name "MANUFACTURER PART NUMBER") "TST-105-01-G-D")
      )
      (libsource (lib "") (part "TP_1"))
    )
    (comp (ref "U5")
      (value "SN74ABT240ADBR")
      (footprint "SOP65P780X200-20N")
      (description "Octal Buffers/Drivers With 3-State Outputs")
      (fields (field (name "MOUSER PART NUMBER") "595-SN74ABT240ADBR"))
      (libsource (lib "Logic") (part "SN74ABT240ADBR"))
    )
    (comp (ref "U6")
      (value "SN74ABT240ADBR")
      (footprint "SOP65P780X200-20N")
      (description "Octal Buffers/Drivers With 3-State Outputs")
      (fields (field (name "MOUSER PART NUMBER") "595-SN74ABT240ADBR"))
      (libsource (lib "Logic") (part "SN74ABT240ADBR"))
    )
    (comp (ref "U7")
      (value "SN74ABT240ADBR")
      (footprint "SOP65P780X200-20N")
      (description "Octal Buffers/Drivers With 3-State Outputs")
      (fields (field (name "MOUSER PART NUMBER") "595-SN74ABT240ADBR"))
      (libsource (lib "Logic") (part "SN74ABT240ADBR"))
    )
    (comp (ref "U8")
      (value "SN74ABT240ADBR")
      (footprint "SOP65P780X200-20N")
      (description "Octal Buffers/Drivers With 3-State Outputs")
      (fields (field (name "MOUSER PART NUMBER") "595-SN74ABT240ADBR"))
      (libsource (lib "Logic") (part "SN74ABT240ADBR"))
    )
  )
  (nets
    (net (code "1") (name "+5") (class "Default")
      (node (ref "R100") (pin "1") (pinfunction "1_1") (pintype "passive"))
      (node (ref "R101") (pin "1") (pinfunction "1_1") (pintype "passive"))
      (node (ref "R102") (pin "1") (pinfunction "1_1") (pintype "passive"))
      (node (ref "R103") (pin "1") (pinfunction "1_1") (pintype "passive"))
      (node (ref "R112") (pin "1") (pinfunction "1_1") (pintype "passive"))
      (node (ref "R113") (pin "1") (pinfunction "1_1") (pintype "passive"))
      (node (ref "R114") (pin "1") (pinfunction "1_1") (pintype "passive"))
      (node (ref "R115") (pin "1") (pinfunction "1_1") (pintype "passive"))
      (node (ref "R116") (pin "1") (pinfunction "1_1") (pintype "passive"))
      (node (ref "R117") (pin "1") (pinfunction "1_1") (pintype "passive"))
      (node (ref "R118") (pin "1") (pinfunction "1_1") (pintype "passive"))
      (node (ref "R119") (pin "1") (pinfunction "1_1") (pintype "passive"))
      (node (ref "R120") (pin "1") (pinfunction "1_1") (pintype "passive"))
      (node (ref "R121") (pin "1") (pinfunction "1_1") (pintype "passive"))
      (node (ref "R122") (pin "1") (pinfunction "1_1") (pintype "passive"))
      (node (ref "R123") (pin "1") (pinfunction "1_1") (pintype "passive"))
      (node (ref "R124") (pin "1") (pinfunction "1_1") (pintype "passive"))
      (node (ref "R125") (pin "1") (pinfunction "1_1") (pintype "passive"))
      (node (ref "R126") (pin "1") (pinfunction "1_1") (pintype "passive"))
      (node (ref "R135") (pin "1") (pinfunction "1_1") (pintype "passive"))
      (node (ref "R136") (pin "1") (pinfunction "1_1") (pintype "passive"))
      (node (ref "R72") (pin "1") (pinfunction "1_1") (pintype "passive"))
      (node (ref "R73") (pin "1") (pinfunction "1_1") (pintype "passive"))
      (node (ref "R74") (pin "1") (pinfunction "1_1") (pintype "passive"))
      (node (ref "R75") (pin "1") (pinfunction "1_1") (pintype "passive"))
      (node (ref "R76") (pin "1") (pinfunction "1_1") (pintype "passive"))
      (node (ref "R77") (pin "1") (pinfunction "1_1") (pintype "passive"))
      (node (ref "R78") (pin "1") (pinfunction "1_1") (pintype "passive"))
      (node (ref "R79") (pin "1") (pinfunction "1_1") (pintype "passive"))
      (node (ref "R80") (pin "2") (pinfunction "2_2") (pintype "passive"))
      (node (ref "R81") (pin "2") (pinfunction "2_2") (pintype "passive"))
      (node (ref "R82") (pin "2") (pinfunction "2_2") (pintype "passive"))
      (node (ref "R83") (pin "2") (pinfunction "2_2") (pintype "passive"))
      (node (ref "R84") (pin "2") (pinfunction "2_2") (pintype "passive"))
      (node (ref "R85") (pin "2") (pinfunction "2_2") (pintype "passive"))
      (node (ref "R86") (pin "2") (pinfunction "2_2") (pintype "passive"))
      (node (ref "R87") (pin "2") (pinfunction "2_2") (pintype "passive"))
      (node (ref "R88") (pin "2") (pinfunction "2_2") (pintype "passive"))
      (node (ref "R89") (pin "2") (pinfunction "2_2") (pintype "passive"))
      (node (ref "R90") (pin "2") (pinfunction "2_2") (pintype "passive"))
      (node (ref "R91") (pin "2") (pinfunction "2_2") (pintype "passive"))
      (node (ref "R92") (pin "2") (pinfunction "2_2") (pintype "passive"))
      (node (ref "R93") (pin "2") (pinfunction "2_2") (pintype "passive"))
      (node (ref "R94") (pin "2") (pinfunction "2_2") (pintype "passive"))
      (node (ref "R95") (pin "2") (pinfunction "2_2") (pintype "passive"))
      (node (ref "R96") (pin "1") (pinfunction "1_1") (pintype "passive"))
      (node (ref "R97") (pin "1") (pinfunction "1_1") (pintype "passive"))
      (node (ref "R98") (pin "1") (pinfunction "1_1") (pintype "passive"))
      (node (ref "R99") (pin "1") (pinfunction "1_1") (pintype "passive"))
      (node (ref "U5") (pin "20") (pinfunction "VCC_20") (pintype "passive"))
      (node (ref "U6") (pin "20") (pinfunction "VCC_20") (pintype "passive"))
      (node (ref "U7") (pin "20") (pinfunction "VCC_20") (pintype "passive"))
      (node (ref "U8") (pin "20") (pinfunction "VCC_20") (pintype "passive"))
    )
    (net (code "2") (name "/A0") (class "Default")
      (node (ref "U5") (pin "2") (pinfunction "1A1_2") (pintype "passive"))
    )
    (net (code "3") (name "/A1") (class "Default")
      (node (ref "U5") (pin "4") (pinfunction "1A2_4") (pintype "passive"))
    )
    (net (code "4") (name "/A2") (class "Default")
      (node (ref "U5") (pin "6") (pinfunction "1A3_6") (pintype "passive"))
    )
    (net (code "5") (name "/A3") (class "Default")
      (node (ref "U5") (pin "8") (pinfunction "1A4_8") (pintype "passive"))
    )
    (net (code "6") (name "/A4") (class "Default")
      (node (ref "U5") (pin "11") (pinfunction "2A1_11") (pintype "passive"))
    )
    (net (code "7") (name "/A5") (class "Default")
      (node (ref "U5") (pin "13") (pinfunction "2A2_13") (pintype "passive"))
    )
    (net (code "8") (name "/A6") (class "Default")
      (node (ref "U5") (pin "15") (pinfunction "2A3_15") (pintype "passive"))
    )
    (net (code "9") (name "/A7") (class "Default")
      (node (ref "U5") (pin "17") (pinfunction "2A4_17") (pintype "passive"))
    )
    (net (code "10") (name "/A8") (class "Default")
      (node (ref "U6") (pin "2") (pinfunction "1A1_2") (pintype "passive"))
    )
    (net (code "11") (name "/A9") (class "Default")
      (node (ref "U6") (pin "4") (pinfunction "1A2_4") (pintype "passive"))
    )
    (net (code "12") (name "/A10") (class "Default")
      (node (ref "U6") (pin "6") (pinfunction "1A3_6") (pintype "passive"))
    )
    (net (code "13") (name "/A11") (class "Default")
      (node (ref "U6") (pin "8") (pinfunction "1A4_8") (pintype "passive"))
    )
    (net (code "14") (name "/A12") (class "Default")
      (node (ref "U6") (pin "11") (pinfunction "2A1_11") (pintype "passive"))
    )
    (net (code "15") (name "/A13") (class "Default")
      (node (ref "U6") (pin "13") (pinfunction "2A2_13") (pintype "passive"))
    )
    (net (code "16") (name "/A14") (class "Default")
      (node (ref "U6") (pin "15") (pinfunction "2A3_15") (pintype "passive"))
    )
    (net (code "17") (name "/A15") (class "Default")
      (node (ref "U6") (pin "17") (pinfunction "2A4_17") (pintype "passive"))
    )
    (net (code "18") (name "/BE") (class "Default")
      (node (ref "U8") (pin "11") (pinfunction "2A1_11") (pintype "passive"))
    )
    (net (code "19") (name "/D0") (class "Default")
      (node (ref "U7") (pin "2") (pinfunction "1A1_2") (pintype "passive"))
    )
    (net (code "20") (name "/D1") (class "Default")
      (node (ref "U7") (pin "4") (pinfunction "1A2_4") (pintype "passive"))
    )
    (net (code "21") (name "/D2") (class "Default")
      (node (ref "U7") (pin "6") (pinfunction "1A3_6") (pintype "passive"))
    )
    (net (code "22") (name "/D3") (class "Default")
      (node (ref "U7") (pin "8") (pinfunction "1A4_8") (pintype "passive"))
    )
    (net (code "23") (name "/D4") (class "Default")
      (node (ref "U7") (pin "11") (pinfunction "2A1_11") (pintype "passive"))
    )
    (net (code "24") (name "/D5") (class "Default")
      (node (ref "U7") (pin "13") (pinfunction "2A2_13") (pintype "passive"))
    )
    (net (code "25") (name "/D6") (class "Default")
      (node (ref "U7") (pin "15") (pinfunction "2A3_15") (pintype "passive"))
    )
    (net (code "26") (name "/D7") (class "Default")
      (node (ref "U7") (pin "17") (pinfunction "2A4_17") (pintype "passive"))
    )
    (net (code "27") (name "/IRQB") (class "Default")
      (node (ref "R138") (pin "1") (pinfunction "1_1") (pintype "passive"))
    )
    (net (code "28") (name "/IRQB0") (class "Default")
      (node (ref "R111") (pin "1") (pinfunction "1_1") (pintype "passive"))
    )
    (net (code "29") (name "/IRQB1") (class "Default")
      (node (ref "R110") (pin "1") (pinfunction "1_1") (pintype "passive"))
    )
    (net (code "30") (name "/IRQB2") (class "Default")
      (node (ref "R109") (pin "1") (pinfunction "1_1") (pintype "passive"))
    )
    (net (code "31") (name "/IRQB3") (class "Default")
      (node (ref "R108") (pin "1") (pinfunction "1_1") (pintype "passive"))
    )
    (net (code "32") (name "/IRQB4") (class "Default")
      (node (ref "R107") (pin "1") (pinfunction "1_1") (pintype "passive"))
    )
    (net (code "33") (name "/IRQB5") (class "Default")
      (node (ref "R106") (pin "1") (pinfunction "1_1") (pintype "passive"))
    )
    (net (code "34") (name "/IRQB6") (class "Default")
      (node (ref "R105") (pin "1") (pinfunction "1_1") (pintype "passive"))
    )
    (net (code "35") (name "/IRQB7") (class "Default")
      (node (ref "R104") (pin "1") (pinfunction "1_1") (pintype "passive"))
    )
    (net (code "36") (name "/PC0") (class "Default")
      (node (ref "R134") (pin "1") (pinfunction "1_1") (pintype "passive"))
    )
    (net (code "37") (name "/PC1") (class "Default")
      (node (ref "R133") (pin "1") (pinfunction "1_1") (pintype "passive"))
    )
    (net (code "38") (name "/PC2") (class "Default")
      (node (ref "R132") (pin "1") (pinfunction "1_1") (pintype "passive"))
    )
    (net (code "39") (name "/PC3") (class "Default")
      (node (ref "R131") (pin "1") (pinfunction "1_1") (pintype "passive"))
    )
    (net (code "40") (name "/PC4") (class "Default")
      (node (ref "R130") (pin "1") (pinfunction "1_1") (pintype "passive"))
    )
    (net (code "41") (name "/PC5") (class "Default")
      (node (ref "R129") (pin "1") (pinfunction "1_1") (pintype "passive"))
    )
    (net (code "42") (name "/PC6") (class "Default")
      (node (ref "R128") (pin "1") (pinfunction "1_1") (pintype "passive"))
    )
    (net (code "43") (name "/PC7") (class "Default")
      (node (ref "R127") (pin "1") (pinfunction "1_1") (pintype "passive"))
    )
    (net (code "44") (name "/Page_0") (class "Default")
      (node (ref "U8") (pin "2") (pinfunction "1A1_2") (pintype "passive"))
    )
    (net (code "45") (name "/Page_1") (class "Default")
      (node (ref "U8") (pin "4") (pinfunction "1A2_4") (pintype "passive"))
    )
    (net (code "46") (name "/Page_2") (class "Default")
      (node (ref "U8") (pin "6") (pinfunction "1A3_6") (pintype "passive"))
    )
    (net (code "47") (name "/Page_3") (class "Default")
      (node (ref "U8") (pin "8") (pinfunction "1A4_8") (pintype "passive"))
    )
    (net (code "48") (name "/RWB") (class "Default")
      (node (ref "U8") (pin "13") (pinfunction "2A2_13") (pintype "passive"))
    )
    (net (code "49") (name "/RWB_Inverted") (class "Default")
      (node (ref "LED38") (pin "1") (pinfunction "K_1") (pintype "passive"))
      (node (ref "U8") (pin "15") (pinfunction "2A3_15") (pintype "passive"))
      (node (ref "U8") (pin "7") (pinfunction "2Y2_7") (pintype "passive"))
    )
    (net (code "50") (name "/nSystemReset") (class "Default")
      (node (ref "R137") (pin "1") (pinfunction "1_1") (pintype "passive"))
    )
    (net (code "51") (name "GND") (class "Default")
      (node (ref "U5") (pin "1") (pinfunction "~{1}OE_1") (pintype "passive"))
      (node (ref "U5") (pin "10") (pinfunction "GND_10") (pintype "passive"))
      (node (ref "U5") (pin "19") (pinfunction "~{2}OE_19") (pintype "passive"))
      (node (ref "U6") (pin "1") (pinfunction "~{1}OE_1") (pintype "passive"))
      (node (ref "U6") (pin "10") (pinfunction "GND_10") (pintype "passive"))
      (node (ref "U6") (pin "19") (pinfunction "~{2}OE_19") (pintype "passive"))
      (node (ref "U7") (pin "1") (pinfunction "~{1}OE_1") (pintype "passive"))
      (node (ref "U7") (pin "10") (pinfunction "GND_10") (pintype "passive"))
      (node (ref "U7") (pin "19") (pinfunction "~{2}OE_19") (pintype "passive"))
      (node (ref "U8") (pin "1") (pinfunction "~{1}OE_1") (pintype "passive"))
      (node (ref "U8") (pin "10") (pinfunction "GND_10") (pintype "passive"))
      (node (ref "U8") (pin "19") (pinfunction "~{2}OE_19") (pintype "passive"))
    )
    (net (code "52") (name "Net-(IRQ0-A)") (class "Default")
      (node (ref "IRQ0") (pin "2") (pinfunction "A_2") (pintype "passive"))
      (node (ref "R79") (pin "2") (pinfunction "2_2") (pintype "passive"))
    )
    (net (code "53") (name "Net-(IRQ0-K)") (class "Default")
      (node (ref "IRQ0") (pin "1") (pinfunction "K_1") (pintype "passive"))
      (node (ref "R111") (pin "2") (pinfunction "2_2") (pintype "passive"))
    )
    (net (code "54") (name "Net-(IRQ1-A)") (class "Default")
      (node (ref "IRQ1") (pin "2") (pinfunction "A_2") (pintype "passive"))
      (node (ref "R78") (pin "2") (pinfunction "2_2") (pintype "passive"))
    )
    (net (code "55") (name "Net-(IRQ1-K)") (class "Default")
      (node (ref "IRQ1") (pin "1") (pinfunction "K_1") (pintype "passive"))
      (node (ref "R110") (pin "2") (pinfunction "2_2") (pintype "passive"))
    )
    (net (code "56") (name "Net-(IRQ2-A)") (class "Default")
      (node (ref "IRQ2") (pin "2") (pinfunction "A_2") (pintype "passive"))
      (node (ref "R77") (pin "2") (pinfunction "2_2") (pintype "passive"))
    )
    (net (code "57") (name "Net-(IRQ2-K)") (class "Default")
      (node (ref "IRQ2") (pin "1") (pinfunction "K_1") (pintype "passive"))
      (node (ref "R109") (pin "2") (pinfunction "2_2") (pintype "passive"))
    )
    (net (code "58") (name "Net-(IRQ3-A)") (class "Default")
      (node (ref "IRQ3") (pin "2") (pinfunction "A_2") (pintype "passive"))
      (node (ref "R76") (pin "2") (pinfunction "2_2") (pintype "passive"))
    )
    (net (code "59") (name "Net-(IRQ3-K)") (class "Default")
      (node (ref "IRQ3") (pin "1") (pinfunction "K_1") (pintype "passive"))
      (node (ref "R108") (pin "2") (pinfunction "2_2") (pintype "passive"))
    )
    (net (code "60") (name "Net-(IRQ4-A)") (class "Default")
      (node (ref "IRQ4") (pin "2") (pinfunction "A_2") (pintype "passive"))
      (node (ref "R75") (pin "2") (pinfunction "2_2") (pintype "passive"))
    )
    (net (code "61") (name "Net-(IRQ4-K)") (class "Default")
      (node (ref "IRQ4") (pin "1") (pinfunction "K_1") (pintype "passive"))
      (node (ref "R107") (pin "2") (pinfunction "2_2") (pintype "passive"))
    )
    (net (code "62") (name "Net-(IRQ5-A)") (class "Default")
      (node (ref "IRQ5") (pin "2") (pinfunction "A_2") (pintype "passive"))
      (node (ref "R74") (pin "2") (pinfunction "2_2") (pintype "passive"))
    )
    (net (code "63") (name "Net-(IRQ5-K)") (class "Default")
      (node (ref "IRQ5") (pin "1") (pinfunction "K_1") (pintype "passive"))
      (node (ref "R106") (pin "2") (pinfunction "2_2") (pintype "passive"))
    )
    (net (code "64") (name "Net-(IRQ6-A)") (class "Default")
      (node (ref "IRQ6") (pin "2") (pinfunction "A_2") (pintype "passive"))
      (node (ref "R73") (pin "2") (pinfunction "2_2") (pintype "passive"))
    )
    (net (code "65") (name "Net-(IRQ6-K)") (class "Default")
      (node (ref "IRQ6") (pin "1") (pinfunction "K_1") (pintype "passive"))
      (node (ref "R105") (pin "2") (pinfunction "2_2") (pintype "passive"))
    )
    (net (code "66") (name "Net-(IRQ7-A)") (class "Default")
      (node (ref "IRQ7") (pin "2") (pinfunction "A_2") (pintype "passive"))
      (node (ref "R72") (pin "2") (pinfunction "2_2") (pintype "passive"))
    )
    (net (code "67") (name "Net-(IRQ7-K)") (class "Default")
      (node (ref "IRQ7") (pin "1") (pinfunction "K_1") (pintype "passive"))
      (node (ref "R104") (pin "2") (pinfunction "2_2") (pintype "passive"))
    )
    (net (code "68") (name "Net-(LED9-A)") (class "Default")
      (node (ref "LED9") (pin "2") (pinfunction "A_2") (pintype "passive"))
      (node (ref "R80") (pin "1") (pinfunction "1_1") (pintype "passive"))
    )
    (net (code "69") (name "Net-(LED9-K)") (class "Default")
      (node (ref "LED9") (pin "1") (pinfunction "K_1") (pintype "passive"))
      (node (ref "U5") (pin "18") (pinfunction "1Y1_18") (pintype "passive"))
    )
    (net (code "70") (name "Net-(LED10-A)") (class "Default")
      (node (ref "LED10") (pin "2") (pinfunction "A_2") (pintype "passive"))
      (node (ref "R81") (pin "1") (pinfunction "1_1") (pintype "passive"))
    )
    (net (code "71") (name "Net-(LED10-K)") (class "Default")
      (node (ref "LED10") (pin "1") (pinfunction "K_1") (pintype "passive"))
      (node (ref "U5") (pin "16") (pinfunction "1Y2_16") (pintype "passive"))
    )
    (net (code "72") (name "Net-(LED11-A)") (class "Default")
      (node (ref "LED11") (pin "2") (pinfunction "A_2") (pintype "passive"))
      (node (ref "R82") (pin "1") (pinfunction "1_1") (pintype "passive"))
    )
    (net (code "73") (name "Net-(LED11-K)") (class "Default")
      (node (ref "LED11") (pin "1") (pinfunction "K_1") (pintype "passive"))
      (node (ref "U5") (pin "14") (pinfunction "1Y3_14") (pintype "passive"))
    )
    (net (code "74") (name "Net-(LED12-A)") (class "Default")
      (node (ref "LED12") (pin "2") (pinfunction "A_2") (pintype "passive"))
      (node (ref "R83") (pin "1") (pinfunction "1_1") (pintype "passive"))
    )
    (net (code "75") (name "Net-(LED12-K)") (class "Default")
      (node (ref "LED12") (pin "1") (pinfunction "K_1") (pintype "passive"))
      (node (ref "U5") (pin "12") (pinfunction "1Y4_12") (pintype "passive"))
    )
    (net (code "76") (name "Net-(LED13-A)") (class "Default")
      (node (ref "LED13") (pin "2") (pinfunction "A_2") (pintype "passive"))
      (node (ref "R84") (pin "1") (pinfunction "1_1") (pintype "passive"))
    )
    (net (code "77") (name "Net-(LED13-K)") (class "Default")
      (node (ref "LED13") (pin "1") (pinfunction "K_1") (pintype "passive"))
      (node (ref "U5") (pin "9") (pinfunction "2Y1_9") (pintype "passive"))
    )
    (net (code "78") (name "Net-(LED14-A)") (class "Default")
      (node (ref "LED14") (pin "2") (pinfunction "A_2") (pintype "passive"))
      (node (ref "R85") (pin "1") (pinfunction "1_1") (pintype "passive"))
    )
    (net (code "79") (name "Net-(LED14-K)") (class "Default")
      (node (ref "LED14") (pin "1") (pinfunction "K_1") (pintype "passive"))
      (node (ref "U5") (pin "7") (pinfunction "2Y2_7") (pintype "passive"))
    )
    (net (code "80") (name "Net-(LED15-A)") (class "Default")
      (node (ref "LED15") (pin "2") (pinfunction "A_2") (pintype "passive"))
      (node (ref "R86") (pin "1") (pinfunction "1_1") (pintype "passive"))
    )
    (net (code "81") (name "Net-(LED15-K)") (class "Default")
      (node (ref "LED15") (pin "1") (pinfunction "K_1") (pintype "passive"))
      (node (ref "U5") (pin "5") (pinfunction "2Y3_5") (pintype "passive"))
    )
    (net (code "82") (name "Net-(LED16-A)") (class "Default")
      (node (ref "LED16") (pin "2") (pinfunction "A_2") (pintype "passive"))
      (node (ref "R87") (pin "1") (pinfunction "1_1") (pintype "passive"))
    )
    (net (code "83") (name "Net-(LED16-K)") (class "Default")
      (node (ref "LED16") (pin "1") (pinfunction "K_1") (pintype "passive"))
      (node (ref "U5") (pin "3") (pinfunction "2Y4_3") (pintype "passive"))
    )
    (net (code "84") (name "Net-(LED17-A)") (class "Default")
      (node (ref "LED17") (pin "2") (pinfunction "A_2") (pintype "passive"))
      (node (ref "R88") (pin "1") (pinfunction "1_1") (pintype "passive"))
    )
    (net (code "85") (name "Net-(LED17-K)") (class "Default")
      (node (ref "LED17") (pin "1") (pinfunction "K_1") (pintype "passive"))
      (node (ref "U6") (pin "18") (pinfunction "1Y1_18") (pintype "passive"))
    )
    (net (code "86") (name "Net-(LED18-A)") (class "Default")
      (node (ref "LED18") (pin "2") (pinfunction "A_2") (pintype "passive"))
      (node (ref "R89") (pin "1") (pinfunction "1_1") (pintype "passive"))
    )
    (net (code "87") (name "Net-(LED18-K)") (class "Default")
      (node (ref "LED18") (pin "1") (pinfunction "K_1") (pintype "passive"))
      (node (ref "U6") (pin "16") (pinfunction "1Y2_16") (pintype "passive"))
    )
    (net (code "88") (name "Net-(LED19-A)") (class "Default")
      (node (ref "LED19") (pin "2") (pinfunction "A_2") (pintype "passive"))
      (node (ref "R90") (pin "1") (pinfunction "1_1") (pintype "passive"))
    )
    (net (code "89") (name "Net-(LED19-K)") (class "Default")
      (node (ref "LED19") (pin "1") (pinfunction "K_1") (pintype "passive"))
      (node (ref "U6") (pin "14") (pinfunction "1Y3_14") (pintype "passive"))
    )
    (net (code "90") (name "Net-(LED20-A)") (class "Default")
      (node (ref "LED20") (pin "2") (pinfunction "A_2") (pintype "passive"))
      (node (ref "R91") (pin "1") (pinfunction "1_1") (pintype "passive"))
    )
    (net (code "91") (name "Net-(LED20-K)") (class "Default")
      (node (ref "LED20") (pin "1") (pinfunction "K_1") (pintype "passive"))
      (node (ref "U6") (pin "12") (pinfunction "1Y4_12") (pintype "passive"))
    )
    (net (code "92") (name "Net-(LED21-A)") (class "Default")
      (node (ref "LED21") (pin "2") (pinfunction "A_2") (pintype "passive"))
      (node (ref "R92") (pin "1") (pinfunction "1_1") (pintype "passive"))
    )
    (net (code "93") (name "Net-(LED21-K)") (class "Default")
      (node (ref "LED21") (pin "1") (pinfunction "K_1") (pintype "passive"))
      (node (ref "U6") (pin "9") (pinfunction "2Y1_9") (pintype "passive"))
    )
    (net (code "94") (name "Net-(LED22-A)") (class "Default")
      (node (ref "LED22") (pin "2") (pinfunction "A_2") (pintype "passive"))
      (node (ref "R93") (pin "1") (pinfunction "1_1") (pintype "passive"))
    )
    (net (code "95") (name "Net-(LED22-K)") (class "Default")
      (node (ref "LED22") (pin "1") (pinfunction "K_1") (pintype "passive"))
      (node (ref "U6") (pin "7") (pinfunction "2Y2_7") (pintype "passive"))
    )
    (net (code "96") (name "Net-(LED23-A)") (class "Default")
      (node (ref "LED23") (pin "2") (pinfunction "A_2") (pintype "passive"))
      (node (ref "R94") (pin "1") (pinfunction "1_1") (pintype "passive"))
    )
    (net (code "97") (name "Net-(LED23-K)") (class "Default")
      (node (ref "LED23") (pin "1") (pinfunction "K_1") (pintype "passive"))
      (node (ref "U6") (pin "5") (pinfunction "2Y3_5") (pintype "passive"))
    )
    (net (code "98") (name "Net-(LED24-A)") (class "Default")
      (node (ref "LED24") (pin "2") (pinfunction "A_2") (pintype "passive"))
      (node (ref "R95") (pin "1") (pinfunction "1_1") (pintype "passive"))
    )
    (net (code "99") (name "Net-(LED24-K)") (class "Default")
      (node (ref "LED24") (pin "1") (pinfunction "K_1") (pintype "passive"))
      (node (ref "U6") (pin "3") (pinfunction "2Y4_3") (pintype "passive"))
    )
    (net (code "100") (name "Net-(LED25-A)") (class "Default")
      (node (ref "LED25") (pin "2") (pinfunction "A_2") (pintype "passive"))
      (node (ref "R96") (pin "2") (pinfunction "2_2") (pintype "passive"))
    )
    (net (code "101") (name "Net-(LED25-K)") (class "Default")
      (node (ref "LED25") (pin "1") (pinfunction "K_1") (pintype "passive"))
      (node (ref "U7") (pin "18") (pinfunction "1Y1_18") (pintype "passive"))
    )
    (net (code "102") (name "Net-(LED26-A)") (class "Default")
      (node (ref "LED26") (pin "2") (pinfunction "A_2") (pintype "passive"))
      (node (ref "R97") (pin "2") (pinfunction "2_2") (pintype "passive"))
    )
    (net (code "103") (name "Net-(LED26-K)") (class "Default")
      (node (ref "LED26") (pin "1") (pinfunction "K_1") (pintype "passive"))
      (node (ref "U7") (pin "16") (pinfunction "1Y2_16") (pintype "passive"))
    )
    (net (code "104") (name "Net-(LED27-A)") (class "Default")
      (node (ref "LED27") (pin "2") (pinfunction "A_2") (pintype "passive"))
      (node (ref "R98") (pin "2") (pinfunction "2_2") (pintype "passive"))
    )
    (net (code "105") (name "Net-(LED27-K)") (class "Default")
      (node (ref "LED27") (pin "1") (pinfunction "K_1") (pintype "passive"))
      (node (ref "U7") (pin "14") (pinfunction "1Y3_14") (pintype "passive"))
    )
    (net (code "106") (name "Net-(LED28-A)") (class "Default")
      (node (ref "LED28") (pin "2") (pinfunction "A_2") (pintype "passive"))
      (node (ref "R99") (pin "2") (pinfunction "2_2") (pintype "passive"))
    )
    (net (code "107") (name "Net-(LED28-K)") (class "Default")
      (node (ref "LED28") (pin "1") (pinfunction "K_1") (pintype "passive"))
      (node (ref "U7") (pin "12") (pinfunction "1Y4_12") (pintype "passive"))
    )
    (net (code "108") (name "Net-(LED29-A)") (class "Default")
      (node (ref "LED29") (pin "2") (pinfunction "A_2") (pintype "passive"))
      (node (ref "R100") (pin "2") (pinfunction "2_2") (pintype "passive"))
    )
    (net (code "109") (name "Net-(LED29-K)") (class "Default")
      (node (ref "LED29") (pin "1") (pinfunction "K_1") (pintype "passive"))
      (node (ref "U7") (pin "9") (pinfunction "2Y1_9") (pintype "passive"))
    )
    (net (code "110") (name "Net-(LED30-A)") (class "Default")
      (node (ref "LED30") (pin "2") (pinfunction "A_2") (pintype "passive"))
      (node (ref "R101") (pin "2") (pinfunction "2_2") (pintype "passive"))
    )
    (net (code "111") (name "Net-(LED30-K)") (class "Default")
      (node (ref "LED30") (pin "1") (pinfunction "K_1") (pintype "passive"))
      (node (ref "U7") (pin "7") (pinfunction "2Y2_7") (pintype "passive"))
    )
    (net (code "112") (name "Net-(LED31-A)") (class "Default")
      (node (ref "LED31") (pin "2") (pinfunction "A_2") (pintype "passive"))
      (node (ref "R102") (pin "2") (pinfunction "2_2") (pintype "passive"))
    )
    (net (code "113") (name "Net-(LED31-K)") (class "Default")
      (node (ref "LED31") (pin "1") (pinfunction "K_1") (pintype "passive"))
      (node (ref "U7") (pin "5") (pinfunction "2Y3_5") (pintype "passive"))
    )
    (net (code "114") (name "Net-(LED32-A)") (class "Default")
      (node (ref "LED32") (pin "2") (pinfunction "A_2") (pintype "passive"))
      (node (ref "R103") (pin "2") (pinfunction "2_2") (pintype "passive"))
    )
    (net (code "115") (name "Net-(LED32-K)") (class "Default")
      (node (ref "LED32") (pin "1") (pinfunction "K_1") (pintype "passive"))
      (node (ref "U7") (pin "3") (pinfunction "2Y4_3") (pintype "passive"))
    )
    (net (code "116") (name "Net-(LED33-A)") (class "Default")
      (node (ref "LED33") (pin "2") (pinfunction "A_2") (pintype "passive"))
      (node (ref "R112") (pin "2") (pinfunction "2_2") (pintype "passive"))
    )
    (net (code "117") (name "Net-(LED33-K)") (class "Default")
      (node (ref "LED33") (pin "1") (pinfunction "K_1") (pintype "passive"))
      (node (ref "U8") (pin "18") (pinfunction "1Y1_18") (pintype "passive"))
    )
    (net (code "118") (name "Net-(LED34-A)") (class "Default")
      (node (ref "LED34") (pin "2") (pinfunction "A_2") (pintype "passive"))
      (node (ref "R113") (pin "2") (pinfunction "2_2") (pintype "passive"))
    )
    (net (code "119") (name "Net-(LED34-K)") (class "Default")
      (node (ref "LED34") (pin "1") (pinfunction "K_1") (pintype "passive"))
      (node (ref "U8") (pin "16") (pinfunction "1Y2_16") (pintype "passive"))
    )
    (net (code "120") (name "Net-(LED35-A)") (class "Default")
      (node (ref "LED35") (pin "2") (pinfunction "A_2") (pintype "passive"))
      (node (ref "R114") (pin "2") (pinfunction "2_2") (pintype "passive"))
    )
    (net (code "121") (name "Net-(LED35-K)") (class "Default")
      (node (ref "LED35") (pin "1") (pinfunction "K_1") (pintype "passive"))
      (node (ref "U8") (pin "14") (pinfunction "1Y3_14") (pintype "passive"))
    )
    (net (code "122") (name "Net-(LED36-A)") (class "Default")
      (node (ref "LED36") (pin "2") (pinfunction "A_2") (pintype "passive"))
      (node (ref "R115") (pin "2") (pinfunction "2_2") (pintype "passive"))
    )
    (net (code "123") (name "Net-(LED36-K)") (class "Default")
      (node (ref "LED36") (pin "1") (pinfunction "K_1") (pintype "passive"))
      (node (ref "U8") (pin "12") (pinfunction "1Y4_12") (pintype "passive"))
    )
    (net (code "124") (name "Net-(LED37-A)") (class "Default")
      (node (ref "LED37") (pin "2") (pinfunction "A_2") (pintype "passive"))
      (node (ref "R116") (pin "2") (pinfunction "2_2") (pintype "passive"))
    )
    (net (code "125") (name "Net-(LED37-K)") (class "Default")
      (node (ref "LED37") (pin "1") (pinfunction "K_1") (pintype "passive"))
      (node (ref "U8") (pin "9") (pinfunction "2Y1_9") (pintype "passive"))
    )
    (net (code "126") (name "Net-(LED38-A)") (class "Default")
      (node (ref "LED38") (pin "2") (pinfunction "A_2") (pintype "passive"))
      (node (ref "R117") (pin "2") (pinfunction "2_2") (pintype "passive"))
    )
    (net (code "127") (name "Net-(LED39-A)") (class "Default")
      (node (ref "LED39") (pin "2") (pinfunction "A_2") (pintype "passive"))
      (node (ref "R118") (pin "2") (pinfunction "2_2") (pintype "passive"))
    )
    (net (code "128") (name "Net-(LED39-K)") (class "Default")
      (node (ref "LED39") (pin "1") (pinfunction "K_1") (pintype "passive"))
      (node (ref "U8") (pin "5") (pinfunction "2Y3_5") (pintype "passive"))
    )
    (net (code "129") (name "Net-(LED48-A)") (class "Default")
      (node (ref "LED48") (pin "2") (pinfunction "A_2") (pintype "passive"))
      (node (ref "R135") (pin "2") (pinfunction "2_2") (pintype "passive"))
    )
    (net (code "130") (name "Net-(LED48-K)") (class "Default")
      (node (ref "LED48") (pin "1") (pinfunction "K_1") (pintype "passive"))
      (node (ref "R137") (pin "2") (pinfunction "2_2") (pintype "passive"))
    )
    (net (code "131") (name "Net-(LED49-A)") (class "Default")
      (node (ref "LED49") (pin "2") (pinfunction "A_2") (pintype "passive"))
      (node (ref "R136") (pin "2") (pinfunction "2_2") (pintype "passive"))
    )
    (net (code "132") (name "Net-(LED49-K)") (class "Default")
      (node (ref "LED49") (pin "1") (pinfunction "K_1") (pintype "passive"))
      (node (ref "R138") (pin "2") (pinfunction "2_2") (pintype "passive"))
    )
    (net (code "133") (name "Net-(PC0-A)") (class "Default")
      (node (ref "PC0") (pin "2") (pinfunction "A_2") (pintype "passive"))
      (node (ref "R126") (pin "2") (pinfunction "2_2") (pintype "passive"))
    )
    (net (code "134") (name "Net-(PC0-K)") (class "Default")
      (node (ref "PC0") (pin "1") (pinfunction "K_1") (pintype "passive"))
      (node (ref "R134") (pin "2") (pinfunction "2_2") (pintype "passive"))
    )
    (net (code "135") (name "Net-(PC1-A)") (class "Default")
      (node (ref "PC1") (pin "2") (pinfunction "A_2") (pintype "passive"))
      (node (ref "R125") (pin "2") (pinfunction "2_2") (pintype "passive"))
    )
    (net (code "136") (name "Net-(PC1-K)") (class "Default")
      (node (ref "PC1") (pin "1") (pinfunction "K_1") (pintype "passive"))
      (node (ref "R133") (pin "2") (pinfunction "2_2") (pintype "passive"))
    )
    (net (code "137") (name "Net-(PC2-A)") (class "Default")
      (node (ref "PC2") (pin "2") (pinfunction "A_2") (pintype "passive"))
      (node (ref "R124") (pin "2") (pinfunction "2_2") (pintype "passive"))
    )
    (net (code "138") (name "Net-(PC2-K)") (class "Default")
      (node (ref "PC2") (pin "1") (pinfunction "K_1") (pintype "passive"))
      (node (ref "R132") (pin "2") (pinfunction "2_2") (pintype "passive"))
    )
    (net (code "139") (name "Net-(PC3-A)") (class "Default")
      (node (ref "PC3") (pin "2") (pinfunction "A_2") (pintype "passive"))
      (node (ref "R123") (pin "2") (pinfunction "2_2") (pintype "passive"))
    )
    (net (code "140") (name "Net-(PC3-K)") (class "Default")
      (node (ref "PC3") (pin "1") (pinfunction "K_1") (pintype "passive"))
      (node (ref "R131") (pin "2") (pinfunction "2_2") (pintype "passive"))
    )
    (net (code "141") (name "Net-(PC4-A)") (class "Default")
      (node (ref "PC4") (pin "2") (pinfunction "A_2") (pintype "passive"))
      (node (ref "R122") (pin "2") (pinfunction "2_2") (pintype "passive"))
    )
    (net (code "142") (name "Net-(PC4-K)") (class "Default")
      (node (ref "PC4") (pin "1") (pinfunction "K_1") (pintype "passive"))
      (node (ref "R130") (pin "2") (pinfunction "2_2") (pintype "passive"))
    )
    (net (code "143") (name "Net-(PC5-A)") (class "Default")
      (node (ref "PC5") (pin "2") (pinfunction "A_2") (pintype "passive"))
      (node (ref "R121") (pin "2") (pinfunction "2_2") (pintype "passive"))
    )
    (net (code "144") (name "Net-(PC5-K)") (class "Default")
      (node (ref "PC5") (pin "1") (pinfunction "K_1") (pintype "passive"))
      (node (ref "R129") (pin "2") (pinfunction "2_2") (pintype "passive"))
    )
    (net (code "145") (name "Net-(PC6-A)") (class "Default")
      (node (ref "PC6") (pin "2") (pinfunction "A_2") (pintype "passive"))
      (node (ref "R120") (pin "2") (pinfunction "2_2") (pintype "passive"))
    )
    (net (code "146") (name "Net-(PC6-K)") (class "Default")
      (node (ref "PC6") (pin "1") (pinfunction "K_1") (pintype "passive"))
      (node (ref "R128") (pin "2") (pinfunction "2_2") (pintype "passive"))
    )
    (net (code "147") (name "Net-(PC7-A)") (class "Default")
      (node (ref "PC7") (pin "2") (pinfunction "A_2") (pintype "passive"))
      (node (ref "R119") (pin "2") (pinfunction "2_2") (pintype "passive"))
    )
    (net (code "148") (name "Net-(PC7-K)") (class "Default")
      (node (ref "PC7") (pin "1") (pinfunction "K_1") (pintype "passive"))
      (node (ref "R127") (pin "2") (pinfunction "2_2") (pintype "passive"))
    )
    (net (code "149") (name "Net-(U8-2A4)") (class "Default")
      (node (ref "TP18") (pin "1") (pinfunction "1_1") (pintype "passive"))
      (node (ref "U8") (pin "17") (pinfunction "2A4_17") (pintype "passive"))
    )
    (net (code "150") (name "Net-(U8-2Y4)") (class "Default")
      (node (ref "TP19") (pin "1") (pinfunction "1_1") (pintype "passive"))
      (node (ref "U8") (pin "3") (pinfunction "2Y4_3") (pintype "passive"))
    )
  )
)
